# AutoDuctMainboard_v1_1.net
KiCad netlist of a schematic drawn in EAGLE
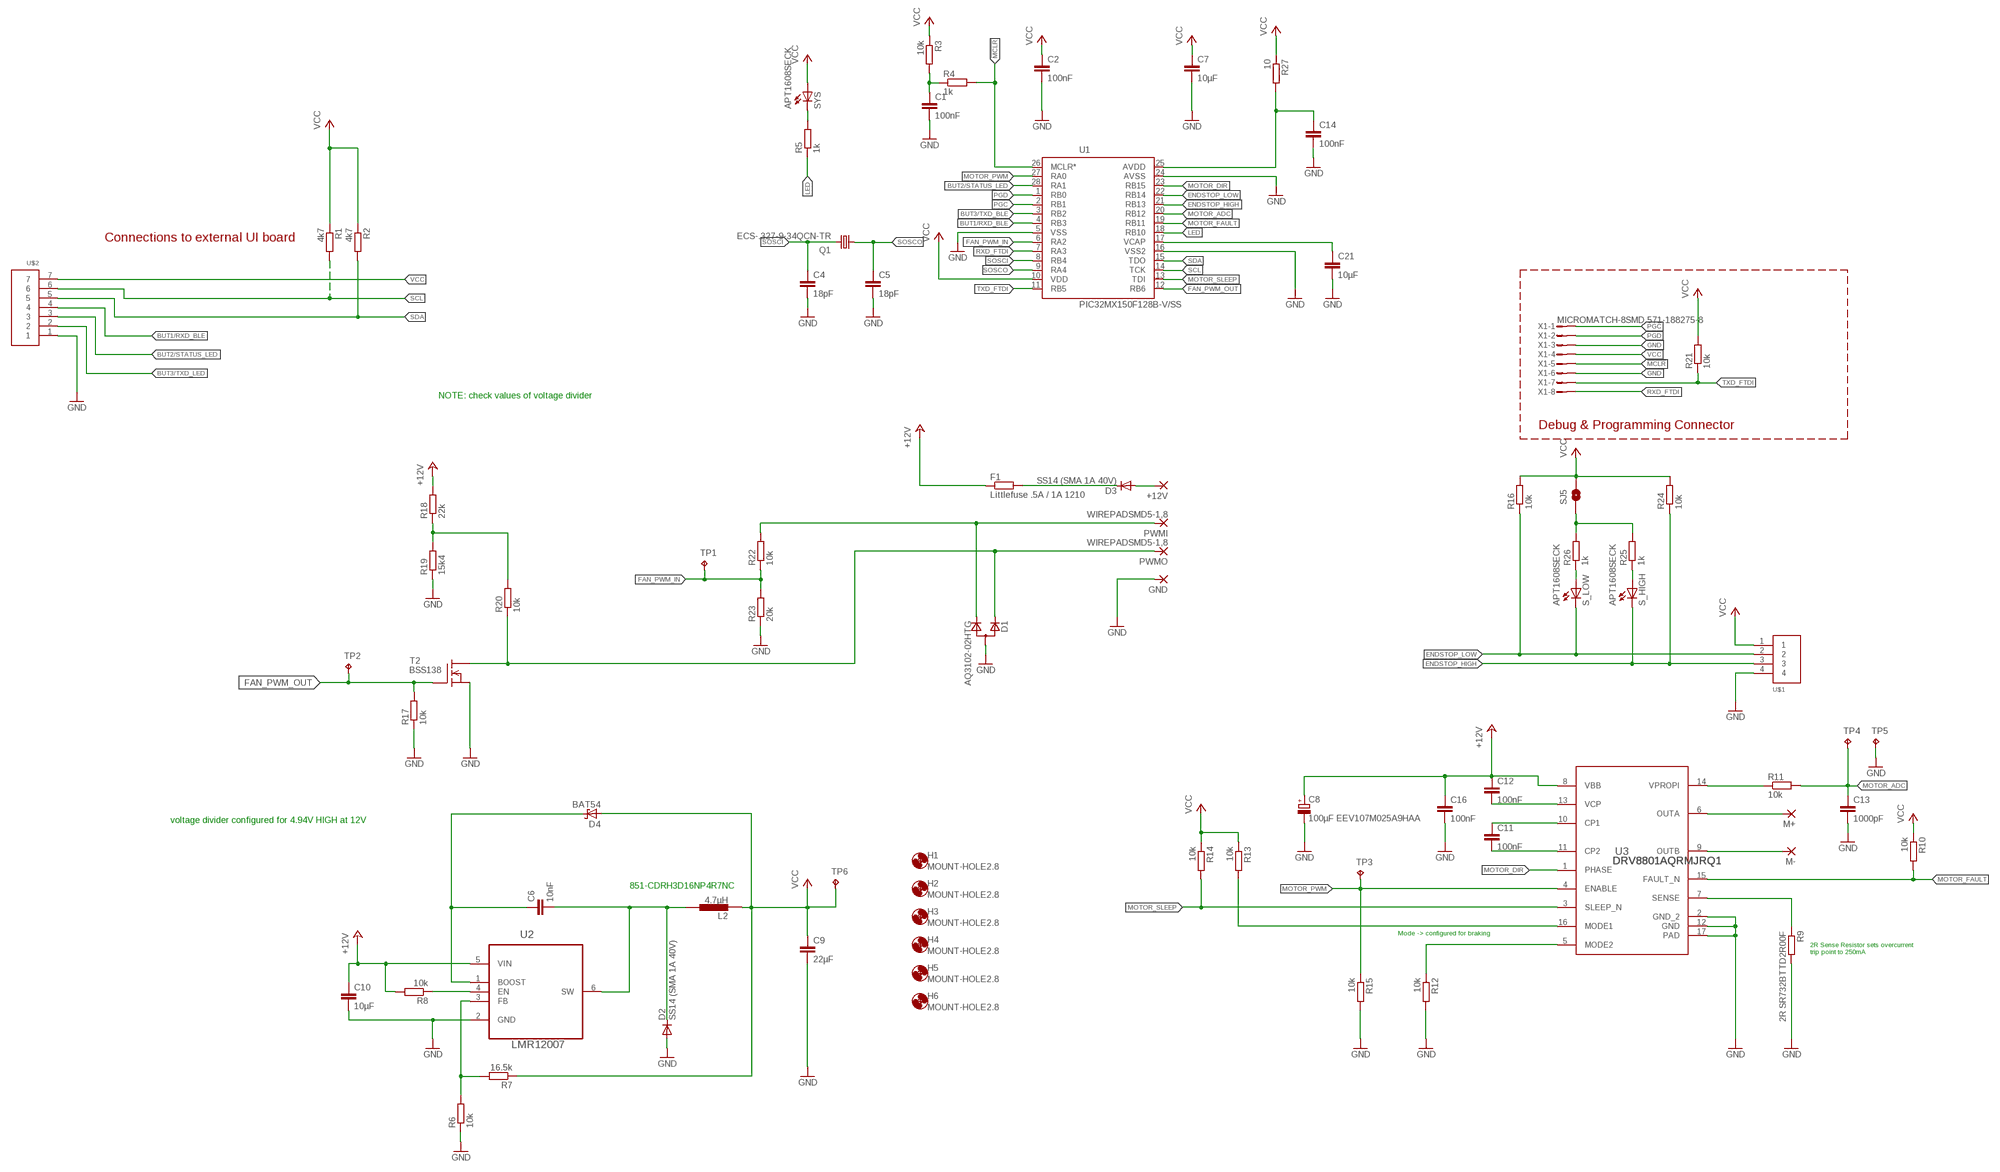
[diagram p0: schematic, sheet 1]

(export (version "E")
  (design (tool "Eeschema 10.0.6"))
  (components
    (comp (ref "+12V")
      (value "SMD5")
      (footprint "eagle-import:SMD2,54-5,08")
      (libsource (lib "eagle-import") (part "SMD5"))
    )
    (comp (ref "C1")
      (value "100nF")
      (footprint "eagle-import:C0402")
      (libsource (lib "eagle-import") (part "C-EUC0402"))
    )
    (comp (ref "C2")
      (value "100nF")
      (footprint "eagle-import:C0402")
      (libsource (lib "eagle-import") (part "C-EUC0402"))
    )
    (comp (ref "C4")
      (value "18pF")
      (footprint "eagle-import:C0603K")
      (libsource (lib "eagle-import") (part "C-EUC0603K"))
    )
    (comp (ref "C5")
      (value "18pF")
      (footprint "eagle-import:C0603K")
      (libsource (lib "eagle-import") (part "C-EUC0603K"))
    )
    (comp (ref "C6")
      (value "10nF")
      (footprint "eagle-import:C0603K")
      (libsource (lib "eagle-import") (part "C-EUC0603K"))
    )
    (comp (ref "C7")
      (value "10µF")
      (footprint "eagle-import:C0603K")
      (libsource (lib "eagle-import") (part "C-EUC0603K"))
    )
    (comp (ref "C8")
      (value "100µF EEV107M025A9HAA")
      (footprint "eagle-import:153CLV-0605")
      (libsource (lib "eagle-import") (part "CPOL-EU153CLV-0605"))
    )
    (comp (ref "C9")
      (value "22µF")
      (footprint "eagle-import:C0805K")
      (libsource (lib "eagle-import") (part "C-EUC0805K"))
    )
    (comp (ref "C10")
      (value "10µF")
      (footprint "eagle-import:C1206K")
      (libsource (lib "eagle-import") (part "C-EUC1206K"))
    )
    (comp (ref "C11")
      (value "100nF")
      (footprint "eagle-import:C0402")
      (libsource (lib "eagle-import") (part "C-EUC0402"))
    )
    (comp (ref "C12")
      (value "100nF")
      (footprint "eagle-import:C0402")
      (libsource (lib "eagle-import") (part "C-EUC0402"))
    )
    (comp (ref "C13")
      (value "1000pF")
      (footprint "eagle-import:C0603K")
      (libsource (lib "eagle-import") (part "C-EUC0603K"))
    )
    (comp (ref "C14")
      (value "100nF")
      (footprint "eagle-import:C0402")
      (libsource (lib "eagle-import") (part "C-EUC0402"))
    )
    (comp (ref "C16")
      (value "100nF")
      (footprint "eagle-import:C0603K")
      (libsource (lib "eagle-import") (part "C-EUC0603K"))
    )
    (comp (ref "C21")
      (value "10µF")
      (footprint "eagle-import:C0603K")
      (libsource (lib "eagle-import") (part "C-EUC0603K"))
    )
    (comp (ref "D1")
      (value "AQ3102-02HTG")
      (footprint "eagle-import:SOT323")
      (libsource (lib "eagle-import") (part "D_2CSOT323"))
    )
    (comp (ref "D2")
      (value "SS14 (SMA 1A 40V)")
      (footprint "eagle-import:DO214AC")
      (libsource (lib "eagle-import") (part "DIODE-DO214AC"))
    )
    (comp (ref "D3")
      (value "SS14 (SMA 1A 40V)")
      (footprint "eagle-import:DO214AC")
      (libsource (lib "eagle-import") (part "DIODE-DO214AC"))
    )
    (comp (ref "D4")
      (value "BAT54")
      (footprint "eagle-import:SOT23")
      (libsource (lib "eagle-import") (part "BAT54"))
    )
    (comp (ref "F1")
      (value "Littlefuse .5A / 1A 1210")
      (footprint "eagle-import:R1210")
      (libsource (lib "eagle-import") (part "resistor_348_R-EU_R1210"))
    )
    (comp (ref "GND")
      (value "SMD5")
      (footprint "eagle-import:SMD2,54-5,08")
      (libsource (lib "eagle-import") (part "SMD5"))
    )
    (comp (ref "H1")
      (value "MOUNT-HOLE2.8")
      (footprint "eagle-import:2,8")
      (libsource (lib "eagle-import") (part "MOUNT-HOLE2.8"))
    )
    (comp (ref "H2")
      (value "MOUNT-HOLE2.8")
      (footprint "eagle-import:2,8")
      (libsource (lib "eagle-import") (part "MOUNT-HOLE2.8"))
    )
    (comp (ref "H3")
      (value "MOUNT-HOLE2.8")
      (footprint "eagle-import:2,8")
      (libsource (lib "eagle-import") (part "MOUNT-HOLE2.8"))
    )
    (comp (ref "H4")
      (value "MOUNT-HOLE2.8")
      (footprint "eagle-import:2,8")
      (libsource (lib "eagle-import") (part "MOUNT-HOLE2.8"))
    )
    (comp (ref "H5")
      (value "MOUNT-HOLE2.8")
      (footprint "eagle-import:2,8")
      (libsource (lib "eagle-import") (part "MOUNT-HOLE2.8"))
    )
    (comp (ref "H6")
      (value "MOUNT-HOLE2.8")
      (footprint "eagle-import:2,8")
      (libsource (lib "eagle-import") (part "MOUNT-HOLE2.8"))
    )
    (comp (ref "L2")
      (value "4.7µH")
      (footprint "eagle-import:CDRH3D16")
      (libsource (lib "eagle-import") (part "CDRH3D16"))
    )
    (comp (ref "M+")
      (value "SMD5")
      (footprint "eagle-import:SMD2,54-5,08")
      (libsource (lib "eagle-import") (part "SMD5"))
    )
    (comp (ref "M-")
      (value "SMD5")
      (footprint "eagle-import:SMD2,54-5,08")
      (libsource (lib "eagle-import") (part "SMD5"))
    )
    (comp (ref "PWMI")
      (value "WIREPADSMD5-1,8")
      (footprint "eagle-import:5-1,8")
      (libsource (lib "eagle-import") (part "WIREPADSMD5-1,8"))
    )
    (comp (ref "PWMO")
      (value "WIREPADSMD5-1,8")
      (footprint "eagle-import:5-1,8")
      (libsource (lib "eagle-import") (part "WIREPADSMD5-1,8"))
    )
    (comp (ref "Q1")
      (value "ECS-.327-9-34QCN-TR")
      (footprint "eagle-import:3.2X1.5")
      (libsource (lib "eagle-import") (part "KX-327-NHF"))
    )
    (comp (ref "R1")
      (value "4k7")
      (footprint "eagle-import:R0603")
      (libsource (lib "eagle-import") (part "rcl_334_R-EU_R0603"))
    )
    (comp (ref "R2")
      (value "4k7")
      (footprint "eagle-import:R0603")
      (libsource (lib "eagle-import") (part "rcl_334_R-EU_R0603"))
    )
    (comp (ref "R3")
      (value "10k")
      (footprint "eagle-import:R0603")
      (libsource (lib "eagle-import") (part "rcl_334_R-EU_R0603"))
    )
    (comp (ref "R4")
      (value "1k")
      (footprint "eagle-import:R0603")
      (libsource (lib "eagle-import") (part "rcl_334_R-EU_R0603"))
    )
    (comp (ref "R5")
      (value "1k")
      (footprint "eagle-import:R0603")
      (libsource (lib "eagle-import") (part "R-EU_R0603"))
    )
    (comp (ref "R6")
      (value "10k")
      (footprint "eagle-import:R0603")
      (libsource (lib "eagle-import") (part "R-EU_R0603"))
    )
    (comp (ref "R7")
      (value "16.5k")
      (footprint "eagle-import:R0603")
      (libsource (lib "eagle-import") (part "R-EU_R0603"))
    )
    (comp (ref "R8")
      (value "10k")
      (footprint "eagle-import:R0603")
      (libsource (lib "eagle-import") (part "R-EU_R0603"))
    )
    (comp (ref "R9")
      (value "2R SR732BTTD2R00F")
      (footprint "eagle-import:R1206")
      (libsource (lib "eagle-import") (part "R-EU_R1206"))
    )
    (comp (ref "R10")
      (value "10k")
      (footprint "eagle-import:R0603")
      (libsource (lib "eagle-import") (part "rcl_334_R-EU_R0603"))
    )
    (comp (ref "R11")
      (value "10k")
      (footprint "eagle-import:R0603")
      (libsource (lib "eagle-import") (part "rcl_334_R-EU_R0603"))
    )
    (comp (ref "R12")
      (value "10k")
      (footprint "eagle-import:R0603")
      (libsource (lib "eagle-import") (part "rcl_334_R-EU_R0603"))
    )
    (comp (ref "R13")
      (value "10k")
      (footprint "eagle-import:R0603")
      (libsource (lib "eagle-import") (part "rcl_334_R-EU_R0603"))
    )
    (comp (ref "R14")
      (value "10k")
      (footprint "eagle-import:R0603")
      (libsource (lib "eagle-import") (part "rcl_334_R-EU_R0603"))
    )
    (comp (ref "R15")
      (value "10k")
      (footprint "eagle-import:R0603")
      (libsource (lib "eagle-import") (part "rcl_334_R-EU_R0603"))
    )
    (comp (ref "R16")
      (value "10k")
      (footprint "eagle-import:R0603")
      (libsource (lib "eagle-import") (part "R-EU_R0603"))
    )
    (comp (ref "R17")
      (value "10k")
      (footprint "eagle-import:R0603")
      (libsource (lib "eagle-import") (part "R-EU_R0603"))
    )
    (comp (ref "R18")
      (value "22k")
      (footprint "eagle-import:R0603")
      (libsource (lib "eagle-import") (part "R-EU_R0603"))
    )
    (comp (ref "R19")
      (value "15k4")
      (footprint "eagle-import:R0603")
      (libsource (lib "eagle-import") (part "R-EU_R0603"))
    )
    (comp (ref "R20")
      (value "10k")
      (footprint "eagle-import:R0603")
      (libsource (lib "eagle-import") (part "R-EU_R0603"))
    )
    (comp (ref "R21")
      (value "10k")
      (footprint "eagle-import:R0603")
      (libsource (lib "eagle-import") (part "R-EU_R0603"))
    )
    (comp (ref "R22")
      (value "10k")
      (footprint "eagle-import:R0603")
      (libsource (lib "eagle-import") (part "R-EU_R0603"))
    )
    (comp (ref "R23")
      (value "20k")
      (footprint "eagle-import:R0603")
      (libsource (lib "eagle-import") (part "R-EU_R0603"))
    )
    (comp (ref "R24")
      (value "10k")
      (footprint "eagle-import:R0603")
      (libsource (lib "eagle-import") (part "R-EU_R0603"))
    )
    (comp (ref "R25")
      (value "1k")
      (footprint "eagle-import:R0603")
      (libsource (lib "eagle-import") (part "R-EU_R0603"))
    )
    (comp (ref "R26")
      (value "1k")
      (footprint "eagle-import:R0603")
      (libsource (lib "eagle-import") (part "R-EU_R0603"))
    )
    (comp (ref "R27")
      (value "10")
      (footprint "eagle-import:R0603")
      (libsource (lib "eagle-import") (part "rcl_334_R-EU_R0603"))
    )
    (comp (ref "SJ5")
      (value "RXLED")
      (footprint "eagle-import:SJ_2S-NO")
      (libsource (lib "eagle-import") (part "SOLDERJUMPERNO"))
    )
    (comp (ref "SYS")
      (value "APT1608SECK")
      (footprint "eagle-import:CHIPLED_0603")
      (libsource (lib "eagle-import") (part "LEDCHIPLED_0603"))
    )
    (comp (ref "S_HIGH")
      (value "APT1608SECK")
      (footprint "eagle-import:CHIPLED_0603")
      (libsource (lib "eagle-import") (part "LEDCHIPLED_0603"))
    )
    (comp (ref "S_LOW")
      (value "APT1608SECK")
      (footprint "eagle-import:CHIPLED_0603")
      (libsource (lib "eagle-import") (part "LEDCHIPLED_0603"))
    )
    (comp (ref "T2")
      (value "BSS138")
      (footprint "eagle-import:SOT23")
      (libsource (lib "eagle-import") (part "BSS138"))
    )
    (comp (ref "TP1")
      (value "TPTP13R")
      (footprint "eagle-import:TP13R")
      (libsource (lib "eagle-import") (part "TPTP13R"))
    )
    (comp (ref "TP2")
      (value "TPTP13R")
      (footprint "eagle-import:TP13R")
      (libsource (lib "eagle-import") (part "TPTP13R"))
    )
    (comp (ref "TP3")
      (value "TPTP13R")
      (footprint "eagle-import:TP13R")
      (libsource (lib "eagle-import") (part "TPTP13R"))
    )
    (comp (ref "TP4")
      (value "TPTP09R")
      (footprint "eagle-import:TP09R")
      (libsource (lib "eagle-import") (part "TPTP09R"))
    )
    (comp (ref "TP5")
      (value "TPTP12SQ")
      (footprint "eagle-import:TP12SQ")
      (libsource (lib "eagle-import") (part "TPTP12SQ"))
    )
    (comp (ref "TP6")
      (value "TPTP13R")
      (footprint "eagle-import:TP13R")
      (libsource (lib "eagle-import") (part "TPTP13R"))
    )
    (comp (ref "U$1")
      (value "WIREPAD1X4")
      (footprint "eagle-import:WIREPAD1X4")
      (libsource (lib "eagle-import") (part "WIREPAD1X4"))
    )
    (comp (ref "U$2")
      (value "WIREPAD1X7")
      (footprint "eagle-import:WIREPAD1X7")
      (libsource (lib "eagle-import") (part "WIREPAD1X7"))
    )
    (comp (ref "U1")
      (value "PIC32MX150F128B-V/SS")
      (footprint "eagle-import:QFN65P600X600X100-29N")
      (fields (field (name "MPN") "PIC32MX130F064B-V/ML "))
      (libsource (lib "eagle-import") (part "PIC32MX/ML130F064B-V"))
    )
    (comp (ref "U2")
      (value "LMR12007")
      (footprint "eagle-import:SOT95P285X100-6N")
      (fields (field (name "MPN") "LM2841XMK-ADJL"))
      (libsource (lib "eagle-import") (part "LMR12007"))
    )
    (comp (ref "U3")
      (value "DRV8801AQRMJRQ1")
      (footprint "eagle-import:RMJ0016A")
      (fields (field (name "COPYRIGHT") "Copyright (C) 2022 Ultra Librarian. All rights reserved."))
      (libsource (lib "eagle-import") (part "DRV8801AQRMJRQ1"))
    )
    (comp (ref "X1")
      (value "MICROMATCH-8SMD 571-188275-8")
      (footprint "eagle-import:MICROMATCH-8-SMD")
      (libsource (lib "eagle-import") (part "MICROMATCH-8SMD"))
    )
  )
  (nets
    (net (code "1") (name "+12V") (class "Default")
      (node (ref "C10") (pin "1") (pinfunction "1_1") (pintype "passive"))
      (node (ref "C12") (pin "1") (pinfunction "1_1") (pintype "passive"))
      (node (ref "C16") (pin "1") (pinfunction "1_1") (pintype "passive"))
      (node (ref "C8") (pin "+") (pinfunction "+_+") (pintype "passive"))
      (node (ref "F1") (pin "1") (pinfunction "1_1") (pintype "passive"))
      (node (ref "R18") (pin "2") (pinfunction "2_2") (pintype "passive"))
      (node (ref "R8") (pin "2") (pinfunction "2_2") (pintype "passive"))
      (node (ref "U2") (pin "5") (pinfunction "VIN_5") (pintype "input"))
      (node (ref "U3") (pin "8") (pinfunction "VBB_8") (pintype "power_in"))
    )
    (net (code "2") (name "/~{MCLR}") (class "Default")
      (node (ref "R4") (pin "2") (pinfunction "2_2") (pintype "passive"))
      (node (ref "U1") (pin "26") (pinfunction "MCLR*_26") (pintype "input"))
      (node (ref "X1") (pin "5") (pinfunction "S_5") (pintype "passive"))
    )
    (net (code "3") (name "BUT1{slash}RXD_BLE") (class "Default")
      (node (ref "U$2") (pin "4") (pinfunction "4_4") (pintype "bidirectional"))
      (node (ref "U1") (pin "4") (pinfunction "RB3_4") (pintype "bidirectional"))
    )
    (net (code "4") (name "BUT2{slash}STATUS_LED") (class "Default")
      (node (ref "U$2") (pin "3") (pinfunction "3_3") (pintype "bidirectional"))
      (node (ref "U1") (pin "28") (pinfunction "RA1_28") (pintype "bidirectional"))
    )
    (net (code "5") (name "BUT3{slash}TXD_BLE") (class "Default")
      (node (ref "U1") (pin "3") (pinfunction "RB2_3") (pintype "bidirectional"))
    )
    (net (code "6") (name "BUT3{slash}TXD_LED") (class "Default")
      (node (ref "U$2") (pin "2") (pinfunction "2_2") (pintype "bidirectional"))
    )
    (net (code "7") (name "ENDSTOP_HIGH") (class "Default")
      (node (ref "R24") (pin "1") (pinfunction "1_1") (pintype "passive"))
      (node (ref "S_HIGH") (pin "C") (pinfunction "C_C") (pintype "passive"))
      (node (ref "U$1") (pin "3") (pinfunction "3_3") (pintype "bidirectional"))
      (node (ref "U1") (pin "21") (pinfunction "RB13_21") (pintype "bidirectional"))
    )
    (net (code "8") (name "ENDSTOP_LOW") (class "Default")
      (node (ref "R16") (pin "1") (pinfunction "1_1") (pintype "passive"))
      (node (ref "S_LOW") (pin "C") (pinfunction "C_C") (pintype "passive"))
      (node (ref "U$1") (pin "2") (pinfunction "2_2") (pintype "bidirectional"))
      (node (ref "U1") (pin "22") (pinfunction "RB14_22") (pintype "bidirectional"))
    )
    (net (code "9") (name "FAN_PWM_IN") (class "Default")
      (node (ref "R22") (pin "1") (pinfunction "1_1") (pintype "passive"))
      (node (ref "R23") (pin "2") (pinfunction "2_2") (pintype "passive"))
      (node (ref "TP1") (pin "TP") (pinfunction "TP_TP") (pintype "input"))
      (node (ref "U1") (pin "6") (pinfunction "RA2_6") (pintype "bidirectional"))
    )
    (net (code "10") (name "FAN_PWM_OUT") (class "Default")
      (node (ref "R17") (pin "2") (pinfunction "2_2") (pintype "passive"))
      (node (ref "T2") (pin "1") (pinfunction "G_1") (pintype "passive"))
      (node (ref "TP2") (pin "TP") (pinfunction "TP_TP") (pintype "input"))
      (node (ref "U1") (pin "12") (pinfunction "RB6_12") (pintype "bidirectional"))
    )
    (net (code "11") (name "GND") (class "Default")
      (node (ref "C1") (pin "2") (pinfunction "2_2") (pintype "passive"))
      (node (ref "C10") (pin "2") (pinfunction "2_2") (pintype "passive"))
      (node (ref "C13") (pin "2") (pinfunction "2_2") (pintype "passive"))
      (node (ref "C14") (pin "2") (pinfunction "2_2") (pintype "passive"))
      (node (ref "C16") (pin "2") (pinfunction "2_2") (pintype "passive"))
      (node (ref "C2") (pin "2") (pinfunction "2_2") (pintype "passive"))
      (node (ref "C21") (pin "2") (pinfunction "2_2") (pintype "passive"))
      (node (ref "C4") (pin "2") (pinfunction "2_2") (pintype "passive"))
      (node (ref "C5") (pin "2") (pinfunction "2_2") (pintype "passive"))
      (node (ref "C7") (pin "2") (pinfunction "2_2") (pintype "passive"))
      (node (ref "C8") (pin "-") (pinfunction "-_-") (pintype "passive"))
      (node (ref "C9") (pin "2") (pinfunction "2_2") (pintype "passive"))
      (node (ref "D1") (pin "1") (pinfunction "A_1") (pintype "passive"))
      (node (ref "D2") (pin "A") (pinfunction "A_A") (pintype "passive"))
      (node (ref "GND") (pin "1") (pinfunction "P_1") (pintype "passive"))
      (node (ref "R12") (pin "2") (pinfunction "2_2") (pintype "passive"))
      (node (ref "R15") (pin "2") (pinfunction "2_2") (pintype "passive"))
      (node (ref "R17") (pin "1") (pinfunction "1_1") (pintype "passive"))
      (node (ref "R19") (pin "1") (pinfunction "1_1") (pintype "passive"))
      (node (ref "R23") (pin "1") (pinfunction "1_1") (pintype "passive"))
      (node (ref "R6") (pin "1") (pinfunction "1_1") (pintype "passive"))
      (node (ref "R9") (pin "2") (pinfunction "2_2") (pintype "passive"))
      (node (ref "T2") (pin "2") (pinfunction "S_2") (pintype "passive"))
      (node (ref "TP5") (pin "TP") (pinfunction "TP_TP") (pintype "input"))
      (node (ref "U$1") (pin "4") (pinfunction "4_4") (pintype "bidirectional"))
      (node (ref "U$2") (pin "1") (pinfunction "1_1") (pintype "bidirectional"))
      (node (ref "U1") (pin "16") (pinfunction "VSS2_16") (pintype "power_in"))
      (node (ref "U1") (pin "24") (pinfunction "AVSS_24") (pintype "power_in"))
      (node (ref "U1") (pin "5") (pinfunction "VSS_5") (pintype "power_in"))
      (node (ref "U2") (pin "2") (pinfunction "GND_2") (pintype "passive"))
      (node (ref "U3") (pin "12") (pinfunction "GND_12") (pintype "power_in"))
      (node (ref "U3") (pin "17") (pinfunction "PAD_17") (pintype "power_in"))
      (node (ref "U3") (pin "2") (pinfunction "GND_2_2") (pintype "power_in"))
      (node (ref "X1") (pin "3") (pinfunction "S_3") (pintype "passive"))
      (node (ref "X1") (pin "6") (pinfunction "S_6") (pintype "passive"))
    )
    (net (code "12") (name "LED") (class "Default")
      (node (ref "R5") (pin "1") (pinfunction "1_1") (pintype "passive"))
      (node (ref "U1") (pin "18") (pinfunction "RB10_18") (pintype "bidirectional"))
    )
    (net (code "13") (name "MOTOR_ADC") (class "Default")
      (node (ref "C13") (pin "1") (pinfunction "1_1") (pintype "passive"))
      (node (ref "R11") (pin "2") (pinfunction "2_2") (pintype "passive"))
      (node (ref "TP4") (pin "TP") (pinfunction "TP_TP") (pintype "input"))
      (node (ref "U1") (pin "20") (pinfunction "RB12_20") (pintype "bidirectional"))
    )
    (net (code "14") (name "MOTOR_DIR") (class "Default")
      (node (ref "U1") (pin "23") (pinfunction "RB15_23") (pintype "bidirectional"))
      (node (ref "U3") (pin "1") (pinfunction "PHASE_1") (pintype "input"))
    )
    (net (code "15") (name "MOTOR_FAULT") (class "Default")
      (node (ref "R10") (pin "2") (pinfunction "2_2") (pintype "passive"))
      (node (ref "U1") (pin "19") (pinfunction "RB11_19") (pintype "bidirectional"))
      (node (ref "U3") (pin "15") (pinfunction "FAULT_N_15") (pintype "open_collector"))
    )
    (net (code "16") (name "MOTOR_PWM") (class "Default")
      (node (ref "R15") (pin "1") (pinfunction "1_1") (pintype "passive"))
      (node (ref "TP3") (pin "TP") (pinfunction "TP_TP") (pintype "input"))
      (node (ref "U1") (pin "27") (pinfunction "RA0_27") (pintype "bidirectional"))
      (node (ref "U3") (pin "4") (pinfunction "ENABLE_4") (pintype "input"))
    )
    (net (code "17") (name "MOTOR_SLEEP") (class "Default")
      (node (ref "R14") (pin "2") (pinfunction "2_2") (pintype "passive"))
      (node (ref "U1") (pin "13") (pinfunction "TDI_13") (pintype "input"))
      (node (ref "U3") (pin "3") (pinfunction "SLEEP_N_3") (pintype "input"))
    )
    (net (code "18") (name "Net-(+12V-P)") (class "Default")
      (node (ref "+12V") (pin "1") (pinfunction "P_1") (pintype "passive"))
      (node (ref "D3") (pin "A") (pinfunction "A_A") (pintype "passive"))
    )
    (net (code "19") (name "Net-(C1-Pad1)") (class "Default")
      (node (ref "C1") (pin "1") (pinfunction "1_1") (pintype "passive"))
      (node (ref "R3") (pin "2") (pinfunction "2_2") (pintype "passive"))
      (node (ref "R4") (pin "1") (pinfunction "1_1") (pintype "passive"))
    )
    (net (code "20") (name "Net-(D1-C1)") (class "Default")
      (node (ref "D1") (pin "2") (pinfunction "C1_2") (pintype "passive"))
      (node (ref "PWMO") (pin "1") (pinfunction "P_1") (pintype "passive"))
      (node (ref "R20") (pin "1") (pinfunction "1_1") (pintype "passive"))
      (node (ref "T2") (pin "3") (pinfunction "D_3") (pintype "passive"))
    )
    (net (code "21") (name "Net-(D1-C2)") (class "Default")
      (node (ref "D1") (pin "3") (pinfunction "C2_3") (pintype "passive"))
      (node (ref "PWMI") (pin "1") (pinfunction "P_1") (pintype "passive"))
      (node (ref "R22") (pin "2") (pinfunction "2_2") (pintype "passive"))
    )
    (net (code "22") (name "Net-(D3-PadC)") (class "Default")
      (node (ref "D3") (pin "C") (pinfunction "C_C") (pintype "passive"))
      (node (ref "F1") (pin "2") (pinfunction "2_2") (pintype "passive"))
    )
    (net (code "23") (name "Net-(D4-C)") (class "Default")
      (node (ref "C6") (pin "1") (pinfunction "1_1") (pintype "passive"))
      (node (ref "D4") (pin "3") (pinfunction "C_3") (pintype "passive"))
      (node (ref "U2") (pin "1") (pinfunction "BOOST_1") (pintype "input"))
    )
    (net (code "24") (name "Net-(M+-P)") (class "Default")
      (node (ref "M+") (pin "1") (pinfunction "P_1") (pintype "passive"))
      (node (ref "U3") (pin "6") (pinfunction "OUTA_6") (pintype "tri_state"))
    )
    (net (code "25") (name "Net-(M--P)") (class "Default")
      (node (ref "M-") (pin "1") (pinfunction "P_1") (pintype "passive"))
      (node (ref "U3") (pin "9") (pinfunction "OUTB_9") (pintype "tri_state"))
    )
    (net (code "26") (name "Net-(R5-Pad2)") (class "Default")
      (node (ref "R5") (pin "2") (pinfunction "2_2") (pintype "passive"))
      (node (ref "SYS") (pin "C") (pinfunction "C_C") (pintype "passive"))
    )
    (net (code "27") (name "Net-(R18-Pad1)") (class "Default")
      (node (ref "R18") (pin "1") (pinfunction "1_1") (pintype "passive"))
      (node (ref "R19") (pin "2") (pinfunction "2_2") (pintype "passive"))
      (node (ref "R20") (pin "2") (pinfunction "2_2") (pintype "passive"))
    )
    (net (code "28") (name "Net-(R25-Pad1)") (class "Default")
      (node (ref "R25") (pin "1") (pinfunction "1_1") (pintype "passive"))
      (node (ref "S_HIGH") (pin "A") (pinfunction "A_A") (pintype "passive"))
    )
    (net (code "29") (name "Net-(R25-Pad2)") (class "Default")
      (node (ref "R25") (pin "2") (pinfunction "2_2") (pintype "passive"))
      (node (ref "R26") (pin "2") (pinfunction "2_2") (pintype "passive"))
      (node (ref "SJ5") (pin "1") (pinfunction "1_1") (pintype "passive"))
    )
    (net (code "30") (name "Net-(R26-Pad1)") (class "Default")
      (node (ref "R26") (pin "1") (pinfunction "1_1") (pintype "passive"))
      (node (ref "S_LOW") (pin "A") (pinfunction "A_A") (pintype "passive"))
    )
    (net (code "31") (name "Net-(U1-AVDD)") (class "Default")
      (node (ref "C14") (pin "1") (pinfunction "1_1") (pintype "passive"))
      (node (ref "R27") (pin "2") (pinfunction "2_2") (pintype "passive"))
      (node (ref "U1") (pin "25") (pinfunction "AVDD_25") (pintype "power_in"))
    )
    (net (code "32") (name "Net-(U1-VCAP)") (class "Default")
      (node (ref "C21") (pin "1") (pinfunction "1_1") (pintype "passive"))
      (node (ref "U1") (pin "17") (pinfunction "VCAP_17") (pintype "power_in"))
    )
    (net (code "33") (name "Net-(U2-EN)") (class "Default")
      (node (ref "R8") (pin "1") (pinfunction "1_1") (pintype "passive"))
      (node (ref "U2") (pin "4") (pinfunction "EN_4") (pintype "input"))
    )
    (net (code "34") (name "Net-(U2-FB)") (class "Default")
      (node (ref "R6") (pin "2") (pinfunction "2_2") (pintype "passive"))
      (node (ref "R7") (pin "2") (pinfunction "2_2") (pintype "passive"))
      (node (ref "U2") (pin "3") (pinfunction "FB_3") (pintype "input"))
    )
    (net (code "35") (name "Net-(U2-SW)") (class "Default")
      (node (ref "C6") (pin "2") (pinfunction "2_2") (pintype "passive"))
      (node (ref "D2") (pin "C") (pinfunction "C_C") (pintype "passive"))
      (node (ref "L2") (pin "2") (pinfunction "2_2") (pintype "passive"))
      (node (ref "U2") (pin "6") (pinfunction "SW_6") (pintype "output"))
    )
    (net (code "36") (name "Net-(U3-CP1)") (class "Default")
      (node (ref "C11") (pin "1") (pinfunction "1_1") (pintype "passive"))
      (node (ref "U3") (pin "10") (pinfunction "CP1_10") (pintype "passive"))
    )
    (net (code "37") (name "Net-(U3-CP2)") (class "Default")
      (node (ref "C11") (pin "2") (pinfunction "2_2") (pintype "passive"))
      (node (ref "U3") (pin "11") (pinfunction "CP2_11") (pintype "passive"))
    )
    (net (code "38") (name "Net-(U3-MODE1)") (class "Default")
      (node (ref "R13") (pin "2") (pinfunction "2_2") (pintype "passive"))
      (node (ref "U3") (pin "16") (pinfunction "MODE1_16") (pintype "input"))
    )
    (net (code "39") (name "Net-(U3-MODE2)") (class "Default")
      (node (ref "R12") (pin "1") (pinfunction "1_1") (pintype "passive"))
      (node (ref "U3") (pin "5") (pinfunction "MODE2_5") (pintype "input"))
    )
    (net (code "40") (name "Net-(U3-SENSE)") (class "Default")
      (node (ref "R9") (pin "1") (pinfunction "1_1") (pintype "passive"))
      (node (ref "U3") (pin "7") (pinfunction "SENSE_7") (pintype "input"))
    )
    (net (code "41") (name "Net-(U3-VCP)") (class "Default")
      (node (ref "C12") (pin "2") (pinfunction "2_2") (pintype "passive"))
      (node (ref "U3") (pin "13") (pinfunction "VCP_13") (pintype "passive"))
    )
    (net (code "42") (name "Net-(U3-VPROPI)") (class "Default")
      (node (ref "R11") (pin "1") (pinfunction "1_1") (pintype "passive"))
      (node (ref "U3") (pin "14") (pinfunction "VPROPI_14") (pintype "output"))
    )
    (net (code "43") (name "PGC") (class "Default")
      (node (ref "U1") (pin "2") (pinfunction "RB1_2") (pintype "bidirectional"))
      (node (ref "X1") (pin "1") (pinfunction "S_1") (pintype "passive"))
    )
    (net (code "44") (name "PGD") (class "Default")
      (node (ref "U1") (pin "1") (pinfunction "RB0_1") (pintype "bidirectional"))
      (node (ref "X1") (pin "2") (pinfunction "S_2") (pintype "passive"))
    )
    (net (code "45") (name "RXD_FTDI") (class "Default")
      (node (ref "U1") (pin "7") (pinfunction "RA3_7") (pintype "bidirectional"))
      (node (ref "X1") (pin "8") (pinfunction "S_8") (pintype "passive"))
    )
    (net (code "46") (name "SCL") (class "Default")
      (node (ref "R1") (pin "2") (pinfunction "2_2") (pintype "passive"))
      (node (ref "U$2") (pin "6") (pinfunction "6_6") (pintype "bidirectional"))
      (node (ref "U1") (pin "14") (pinfunction "TCK_14") (pintype "input"))
    )
    (net (code "47") (name "SDA") (class "Default")
      (node (ref "R2") (pin "2") (pinfunction "2_2") (pintype "passive"))
      (node (ref "U$2") (pin "5") (pinfunction "5_5") (pintype "bidirectional"))
      (node (ref "U1") (pin "15") (pinfunction "TDO_15") (pintype "output"))
    )
    (net (code "48") (name "SOSCI") (class "Default")
      (node (ref "C4") (pin "1") (pinfunction "1_1") (pintype "passive"))
      (node (ref "Q1") (pin "2") (pinfunction "2_2") (pintype "passive"))
      (node (ref "U1") (pin "8") (pinfunction "RB4_8") (pintype "bidirectional"))
    )
    (net (code "49") (name "SOSCO") (class "Default")
      (node (ref "C5") (pin "1") (pinfunction "1_1") (pintype "passive"))
      (node (ref "Q1") (pin "1") (pinfunction "1_1") (pintype "passive"))
      (node (ref "U1") (pin "9") (pinfunction "RA4_9") (pintype "bidirectional"))
    )
    (net (code "50") (name "TXD_FTDI") (class "Default")
      (node (ref "R21") (pin "1") (pinfunction "1_1") (pintype "passive"))
      (node (ref "U1") (pin "11") (pinfunction "RB5_11") (pintype "bidirectional"))
      (node (ref "X1") (pin "7") (pinfunction "S_7") (pintype "passive"))
    )
    (net (code "51") (name "VCC") (class "Default")
      (node (ref "C2") (pin "1") (pinfunction "1_1") (pintype "passive"))
      (node (ref "C7") (pin "1") (pinfunction "1_1") (pintype "passive"))
      (node (ref "C9") (pin "1") (pinfunction "1_1") (pintype "passive"))
      (node (ref "D4") (pin "1") (pinfunction "A_1") (pintype "passive"))
      (node (ref "L2") (pin "1") (pinfunction "1_1") (pintype "passive"))
      (node (ref "R1") (pin "1") (pinfunction "1_1") (pintype "passive"))
      (node (ref "R10") (pin "1") (pinfunction "1_1") (pintype "passive"))
      (node (ref "R13") (pin "1") (pinfunction "1_1") (pintype "passive"))
      (node (ref "R14") (pin "1") (pinfunction "1_1") (pintype "passive"))
      (node (ref "R16") (pin "2") (pinfunction "2_2") (pintype "passive"))
      (node (ref "R2") (pin "1") (pinfunction "1_1") (pintype "passive"))
      (node (ref "R21") (pin "2") (pinfunction "2_2") (pintype "passive"))
      (node (ref "R24") (pin "2") (pinfunction "2_2") (pintype "passive"))
      (node (ref "R27") (pin "1") (pinfunction "1_1") (pintype "passive"))
      (node (ref "R3") (pin "1") (pinfunction "1_1") (pintype "passive"))
      (node (ref "R7") (pin "1") (pinfunction "1_1") (pintype "passive"))
      (node (ref "SJ5") (pin "2") (pinfunction "2_2") (pintype "passive"))
      (node (ref "SYS") (pin "A") (pinfunction "A_A") (pintype "passive"))
      (node (ref "TP6") (pin "TP") (pinfunction "TP_TP") (pintype "input"))
      (node (ref "U$1") (pin "1") (pinfunction "1_1") (pintype "bidirectional"))
      (node (ref "U$2") (pin "7") (pinfunction "7_7") (pintype "bidirectional"))
      (node (ref "U1") (pin "10") (pinfunction "VDD_10") (pintype "power_in"))
      (node (ref "X1") (pin "4") (pinfunction "S_4") (pintype "passive"))
    )
  )
)
